# Sheet_1_2025-11-09.net
KiCad netlist of a schematic drawn in Altium Designer
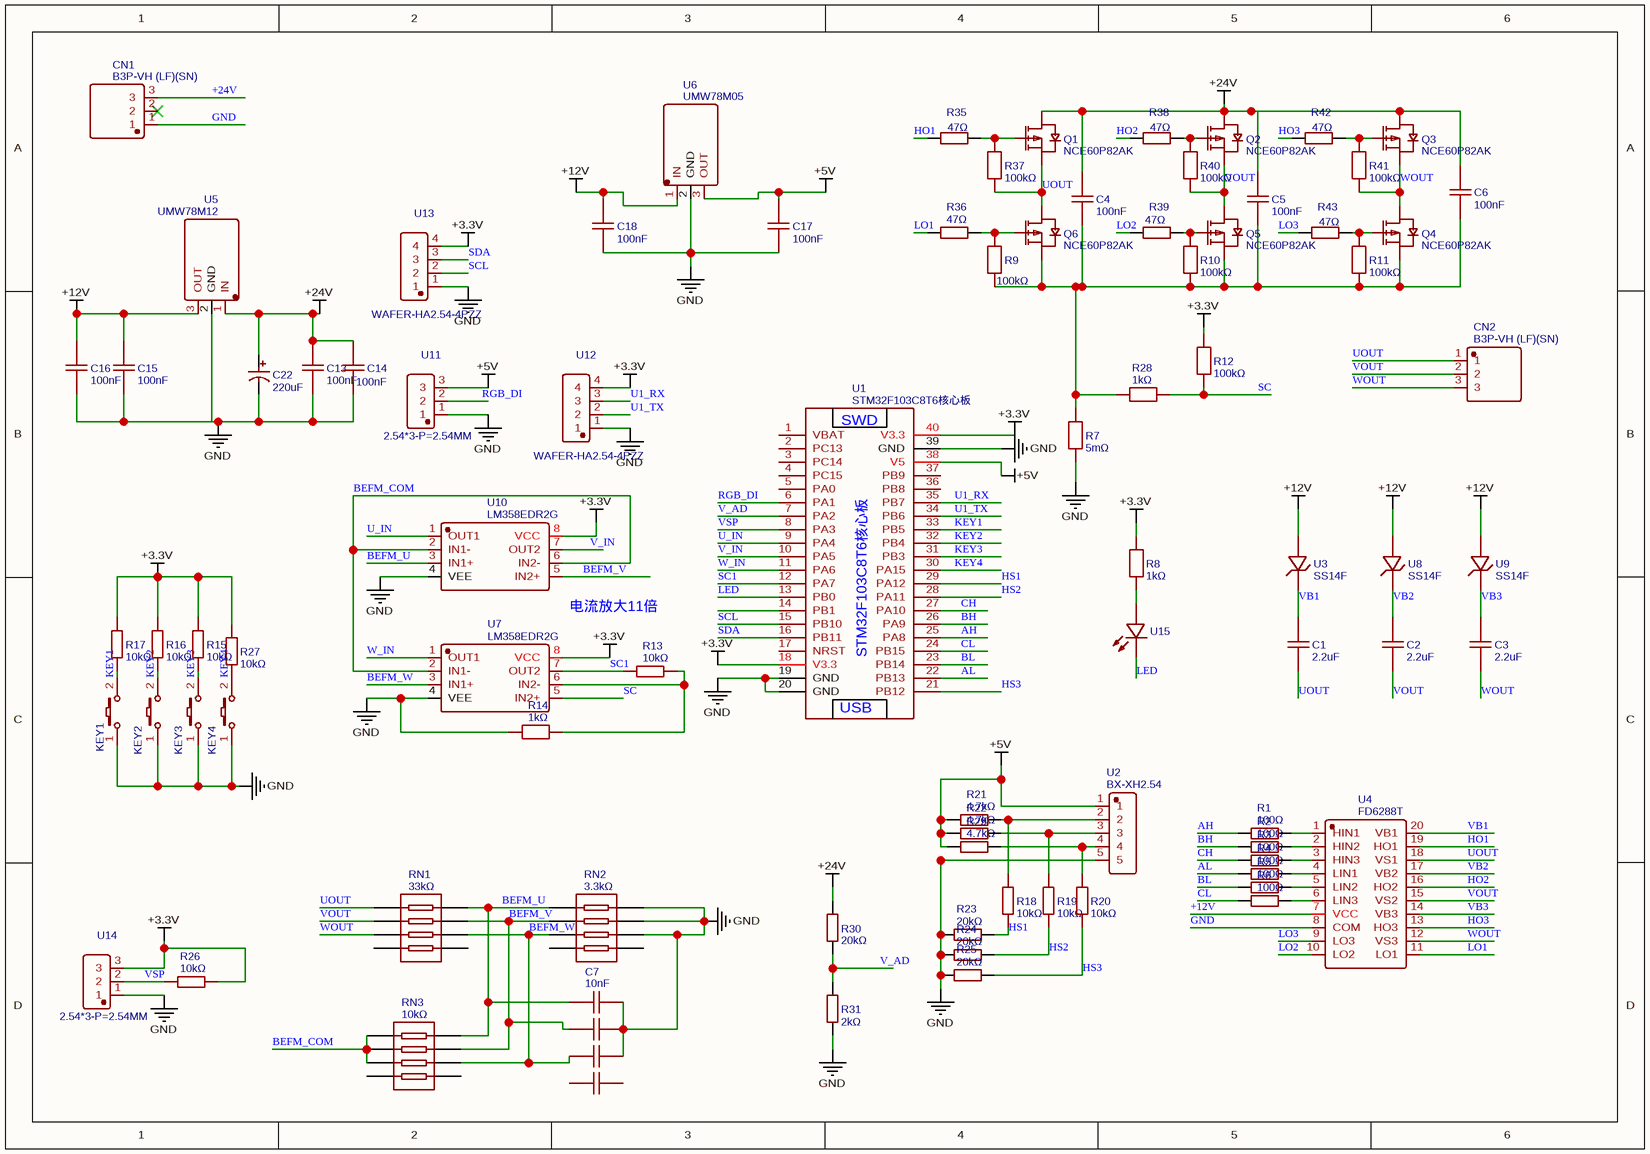
[diagram p0: Sheet_1_2025-11-09.schdoc]

(export (version "E")
  (design (tool "Eeschema 10.0.6"))
  (components
    (comp (ref "C1")
      (value "2.2uF")
      (fields
        (field (name "MANUFACTURER") "CCTC(三环)")
        (field (name "MANUFACTURER PART") "TCC0805X5R225K250FT")
        (field (name "CONTRIBUTOR") "lcsc")
      )
      (libsource (lib "altium-import") (part "root_1_2.2uF_"))
    )
    (comp (ref "C2")
      (value "2.2uF")
      (fields
        (field (name "MANUFACTURER") "CCTC(三环)")
        (field (name "MANUFACTURER PART") "TCC0805X5R225K250FT")
        (field (name "CONTRIBUTOR") "lcsc")
      )
      (libsource (lib "altium-import") (part "root_1_2.2uF_"))
    )
    (comp (ref "C3")
      (value "2.2uF")
      (fields
        (field (name "MANUFACTURER") "CCTC(三环)")
        (field (name "MANUFACTURER PART") "TCC0805X5R225K250FT")
        (field (name "CONTRIBUTOR") "lcsc")
      )
      (libsource (lib "altium-import") (part "root_1_2.2uF_"))
    )
    (comp (ref "C4")
      (value "100nF")
      (fields
        (field (name "MANUFACTURER PART") "CT41-0603-2F4-50V-0.1uF-M(N)")
        (field (name "CONTRIBUTOR") "LCSC")
      )
      (libsource (lib "altium-import") (part "root_0_100nF_"))
    )
    (comp (ref "C5")
      (value "100nF")
      (fields
        (field (name "MANUFACTURER PART") "CT41-0603-2F4-50V-0.1uF-M(N)")
        (field (name "CONTRIBUTOR") "LCSC")
      )
      (libsource (lib "altium-import") (part "root_0_100nF_"))
    )
    (comp (ref "C6")
      (value "100nF")
      (fields
        (field (name "MANUFACTURER PART") "CT41-0603-2F4-50V-0.1uF-M(N)")
        (field (name "CONTRIBUTOR") "LCSC")
      )
      (libsource (lib "altium-import") (part "root_0_100nF_"))
    )
    (comp (ref "C7")
      (value "10nF")
      (fields
        (field (name "MANUFACTURER") "YAGEO(国巨)")
        (field (name "MANUFACTURER PART") "CA0612KRX7R9BB103")
        (field (name "CONTRIBUTOR") "LCSC")
      )
      (libsource (lib "altium-import") (part "root_1_10nF_"))
    )
    (comp (ref "C13")
      (value "100nF")
      (fields
        (field (name "MANUFACTURER") "XINNA(新纳)")
        (field (name "MANUFACTURER PART") "CT063X7R104KNTD")
        (field (name "CONTRIBUTOR") "lcsc")
      )
      (libsource (lib "altium-import") (part "root_1_100nF_"))
    )
    (comp (ref "C14")
      (value "100nF")
      (fields
        (field (name "MANUFACTURER") "XINNA(新纳)")
        (field (name "MANUFACTURER PART") "CT063X7R104KNTD")
        (field (name "CONTRIBUTOR") "lcsc")
      )
      (libsource (lib "altium-import") (part "root_1_100nF_"))
    )
    (comp (ref "C15")
      (value "100nF")
      (fields
        (field (name "MANUFACTURER") "XINNA(新纳)")
        (field (name "MANUFACTURER PART") "CT063X7R104KNTD")
        (field (name "CONTRIBUTOR") "lcsc")
      )
      (libsource (lib "altium-import") (part "root_1_100nF_"))
    )
    (comp (ref "C16")
      (value "100nF")
      (fields
        (field (name "MANUFACTURER") "XINNA(新纳)")
        (field (name "MANUFACTURER PART") "CT063X7R104KNTD")
        (field (name "CONTRIBUTOR") "lcsc")
      )
      (libsource (lib "altium-import") (part "root_1_100nF_"))
    )
    (comp (ref "C17")
      (value "100nF")
      (fields
        (field (name "MANUFACTURER") "XINNA(新纳)")
        (field (name "MANUFACTURER PART") "CT063X7R104KNTD")
        (field (name "CONTRIBUTOR") "lcsc")
      )
      (libsource (lib "altium-import") (part "root_1_100nF_"))
    )
    (comp (ref "C18")
      (value "100nF")
      (fields
        (field (name "MANUFACTURER") "XINNA(新纳)")
        (field (name "MANUFACTURER PART") "CT063X7R104KNTD")
        (field (name "CONTRIBUTOR") "lcsc")
      )
      (libsource (lib "altium-import") (part "root_1_100nF_"))
    )
    (comp (ref "C22")
      (value "220uF")
      (fields
        (field (name "MANUFACTURER") "rubycon(红宝石)")
        (field (name "MANUFACTURER PART") "100PX220MEFC12.5X20")
      )
      (libsource (lib "altium-import") (part "root_3_220uF_"))
    )
    (comp (ref "CN1")
      (value "B3P-VH (LF)(SN)")
      (fields
        (field (name "MANUFACTURER") "JST")
        (field (name "MANUFACTURER PART") "B3P-VH(LF)(SN)")
        (field (name "CONTRIBUTOR") "LCSC")
      )
      (libsource (lib "altium-import") (part "root_2_B3P-VH (LF)(SN)_"))
    )
    (comp (ref "CN2")
      (value "B3P-VH (LF)(SN)")
      (fields
        (field (name "MANUFACTURER") "JST")
        (field (name "MANUFACTURER PART") "B3P-VH(LF)(SN)")
        (field (name "CONTRIBUTOR") "LCSC")
      )
      (libsource (lib "altium-import") (part "root_0_B3P-VH (LF)(SN)_"))
    )
    (comp (ref "KEY1")
      (value "K2-3.6×6.1_SMD")
      (fields (field (name "MANUFACTURER PART") "K2-1107ST-A4SW-06") (field (name "CONTRIBUTOR") "LCEDA_Lib"))
      (libsource (lib "altium-import") (part "root_1_K2-3.6×6.1_SMD_"))
    )
    (comp (ref "KEY2")
      (value "K2-3.6×6.1_SMD")
      (fields (field (name "MANUFACTURER PART") "K2-1107ST-A4SW-06") (field (name "CONTRIBUTOR") "LCEDA_Lib"))
      (libsource (lib "altium-import") (part "root_1_K2-3.6×6.1_SMD_"))
    )
    (comp (ref "KEY3")
      (value "K2-3.6×6.1_SMD")
      (fields (field (name "MANUFACTURER PART") "K2-1107ST-A4SW-06") (field (name "CONTRIBUTOR") "LCEDA_Lib"))
      (libsource (lib "altium-import") (part "root_1_K2-3.6×6.1_SMD_"))
    )
    (comp (ref "KEY4")
      (value "K2-3.6×6.1_SMD")
      (fields (field (name "MANUFACTURER PART") "K2-1107ST-A4SW-06") (field (name "CONTRIBUTOR") "LCEDA_Lib"))
      (libsource (lib "altium-import") (part "root_1_K2-3.6×6.1_SMD_"))
    )
    (comp (ref "Q1")
      (value "NCE60P82AK")
      (fields (field (name "MANUFACTURER") "NCE(无锡新洁能)") (field (name "CONTRIBUTOR") "lcsc"))
      (libsource (lib "altium-import") (part "root_0_NCE60P82AK_"))
    )
    (comp (ref "Q2")
      (value "NCE60P82AK")
      (fields (field (name "MANUFACTURER") "NCE(无锡新洁能)") (field (name "CONTRIBUTOR") "lcsc"))
      (libsource (lib "altium-import") (part "root_0_NCE60P82AK_"))
    )
    (comp (ref "Q3")
      (value "NCE60P82AK")
      (fields (field (name "MANUFACTURER") "NCE(无锡新洁能)") (field (name "CONTRIBUTOR") "lcsc"))
      (libsource (lib "altium-import") (part "root_0_NCE60P82AK_"))
    )
    (comp (ref "Q4")
      (value "NCE60P82AK")
      (fields (field (name "MANUFACTURER") "NCE(无锡新洁能)") (field (name "CONTRIBUTOR") "lcsc"))
      (libsource (lib "altium-import") (part "root_0_NCE60P82AK_"))
    )
    (comp (ref "Q5")
      (value "NCE60P82AK")
      (fields (field (name "MANUFACTURER") "NCE(无锡新洁能)") (field (name "CONTRIBUTOR") "lcsc"))
      (libsource (lib "altium-import") (part "root_0_NCE60P82AK_"))
    )
    (comp (ref "Q6")
      (value "NCE60P82AK")
      (fields (field (name "MANUFACTURER") "NCE(无锡新洁能)") (field (name "CONTRIBUTOR") "lcsc"))
      (libsource (lib "altium-import") (part "root_0_NCE60P82AK_"))
    )
    (comp (ref "R1")
      (value "100Ω")
      (fields
        (field (name "MANUFACTURER") "UNI-ROYAL(厚声)")
        (field (name "MANUFACTURER PART") "0603WAF1000T5E")
      )
      (libsource (lib "altium-import") (part "root_0_100Ω_"))
    )
    (comp (ref "R2")
      (value "100Ω")
      (fields
        (field (name "MANUFACTURER") "UNI-ROYAL(厚声)")
        (field (name "MANUFACTURER PART") "0603WAF1000T5E")
      )
      (libsource (lib "altium-import") (part "root_0_100Ω_"))
    )
    (comp (ref "R3")
      (value "100Ω")
      (fields
        (field (name "MANUFACTURER") "UNI-ROYAL(厚声)")
        (field (name "MANUFACTURER PART") "0603WAF1000T5E")
      )
      (libsource (lib "altium-import") (part "root_0_100Ω_"))
    )
    (comp (ref "R4")
      (value "100Ω")
      (fields
        (field (name "MANUFACTURER") "UNI-ROYAL(厚声)")
        (field (name "MANUFACTURER PART") "0603WAF1000T5E")
      )
      (libsource (lib "altium-import") (part "root_0_100Ω_"))
    )
    (comp (ref "R5")
      (value "100Ω")
      (fields
        (field (name "MANUFACTURER") "UNI-ROYAL(厚声)")
        (field (name "MANUFACTURER PART") "0603WAF1000T5E")
      )
      (libsource (lib "altium-import") (part "root_0_100Ω_"))
    )
    (comp (ref "R6")
      (value "100Ω")
      (fields
        (field (name "MANUFACTURER") "UNI-ROYAL(厚声)")
        (field (name "MANUFACTURER PART") "0603WAF1000T5E")
      )
      (libsource (lib "altium-import") (part "root_0_100Ω_"))
    )
    (comp (ref "R7")
      (value "5mΩ")
      (fields
        (field (name "MANUFACTURER") "Milliohm(毫欧)")
        (field (name "MANUFACTURER PART") "HoLR2512-1.5W-100mR-1%-15ppm")
        (field (name "CONTRIBUTOR") "LCSC")
      )
      (libsource (lib "altium-import") (part "root_1_5mΩ_"))
    )
    (comp (ref "R8")
      (value "1kΩ")
      (fields
        (field (name "MANUFACTURER") "TE Connectivity(泰科电子)")
        (field (name "MANUFACTURER PART") "CPF0603B10KE1")
        (field (name "CONTRIBUTOR") "lcsc")
      )
      (libsource (lib "altium-import") (part "root_1_1kΩ_"))
    )
    (comp (ref "R9")
      (value "100kΩ")
      (fields
        (field (name "MANUFACTURER") "Milliohm(毫欧)")
        (field (name "MANUFACTURER PART") "HoAR0603-1/10W-100KR-1%-TCR25")
        (field (name "CONTRIBUTOR") "lcsc")
      )
      (libsource (lib "altium-import") (part "root_1_100kΩ_"))
    )
    (comp (ref "R10")
      (value "100kΩ")
      (fields
        (field (name "MANUFACTURER") "Milliohm(毫欧)")
        (field (name "MANUFACTURER PART") "HoAR0603-1/10W-100KR-1%-TCR25")
        (field (name "CONTRIBUTOR") "lcsc")
      )
      (libsource (lib "altium-import") (part "root_1_100kΩ_"))
    )
    (comp (ref "R11")
      (value "100kΩ")
      (fields
        (field (name "MANUFACTURER") "Milliohm(毫欧)")
        (field (name "MANUFACTURER PART") "HoAR0603-1/10W-100KR-1%-TCR25")
        (field (name "CONTRIBUTOR") "lcsc")
      )
      (libsource (lib "altium-import") (part "root_1_100kΩ_"))
    )
    (comp (ref "R12")
      (value "100kΩ")
      (fields
        (field (name "MANUFACTURER") "TE Connectivity(泰科电子)")
        (field (name "MANUFACTURER PART") "CPF0603B10KE1")
        (field (name "CONTRIBUTOR") "lcsc")
      )
      (libsource (lib "altium-import") (part "root_1_100kΩ_"))
    )
    (comp (ref "R13")
      (value "10kΩ")
      (fields
        (field (name "MANUFACTURER") "Tyohm(幸亚电阻)")
        (field (name "MANUFACTURER PART") "RMC060310KFN")
        (field (name "CONTRIBUTOR") "LCSC")
      )
      (libsource (lib "altium-import") (part "root_0_10kΩ_"))
    )
    (comp (ref "R14")
      (value "1kΩ")
      (fields
        (field (name "MANUFACTURER") "VO(翔胜)")
        (field (name "MANUFACTURER PART") "FCR0603F1K")
        (field (name "CONTRIBUTOR") "lcsc")
      )
      (libsource (lib "altium-import") (part "root_0_1kΩ_"))
    )
    (comp (ref "R15")
      (value "10kΩ")
      (fields
        (field (name "MANUFACTURER") "Tyohm(幸亚电阻)")
        (field (name "MANUFACTURER PART") "RMC060310KFN")
        (field (name "CONTRIBUTOR") "LCSC")
      )
      (libsource (lib "altium-import") (part "root_1_10kΩ_"))
    )
    (comp (ref "R16")
      (value "10kΩ")
      (fields
        (field (name "MANUFACTURER") "Tyohm(幸亚电阻)")
        (field (name "MANUFACTURER PART") "RMC060310KFN")
        (field (name "CONTRIBUTOR") "LCSC")
      )
      (libsource (lib "altium-import") (part "root_1_10kΩ_"))
    )
    (comp (ref "R17")
      (value "10kΩ")
      (fields
        (field (name "MANUFACTURER") "Tyohm(幸亚电阻)")
        (field (name "MANUFACTURER PART") "RMC060310KFN")
        (field (name "CONTRIBUTOR") "LCSC")
      )
      (libsource (lib "altium-import") (part "root_1_10kΩ_"))
    )
    (comp (ref "R18")
      (value "10kΩ")
      (fields
        (field (name "MANUFACTURER") "Tyohm(幸亚电阻)")
        (field (name "MANUFACTURER PART") "RMC060310KFN")
        (field (name "CONTRIBUTOR") "LCSC")
      )
      (libsource (lib "altium-import") (part "root_1_10kΩ_"))
    )
    (comp (ref "R19")
      (value "10kΩ")
      (fields
        (field (name "MANUFACTURER") "Tyohm(幸亚电阻)")
        (field (name "MANUFACTURER PART") "RMC060310KFN")
        (field (name "CONTRIBUTOR") "LCSC")
      )
      (libsource (lib "altium-import") (part "root_1_10kΩ_"))
    )
    (comp (ref "R20")
      (value "10kΩ")
      (fields
        (field (name "MANUFACTURER") "Tyohm(幸亚电阻)")
        (field (name "MANUFACTURER PART") "RMC060310KFN")
        (field (name "CONTRIBUTOR") "LCSC")
      )
      (libsource (lib "altium-import") (part "root_1_10kΩ_"))
    )
    (comp (ref "R21")
      (value "4.7kΩ")
      (fields
        (field (name "MANUFACTURER") "UNI-ROYAL(厚声)")
        (field (name "MANUFACTURER PART") "0603WAF4701T5E")
      )
      (libsource (lib "altium-import") (part "root_2_4.7kΩ_"))
    )
    (comp (ref "R22")
      (value "4.7kΩ")
      (fields
        (field (name "MANUFACTURER") "UNI-ROYAL(厚声)")
        (field (name "MANUFACTURER PART") "0603WAF4701T5E")
      )
      (libsource (lib "altium-import") (part "root_2_4.7kΩ_"))
    )
    (comp (ref "R23")
      (value "20kΩ")
      (fields
        (field (name "MANUFACTURER") "UNI-ROYAL(厚声)")
        (field (name "MANUFACTURER PART") "0603WAF2002T5E")
      )
      (libsource (lib "altium-import") (part "root_2_20kΩ_"))
    )
    (comp (ref "R24")
      (value "20kΩ")
      (fields
        (field (name "MANUFACTURER") "UNI-ROYAL(厚声)")
        (field (name "MANUFACTURER PART") "0603WAF2002T5E")
      )
      (libsource (lib "altium-import") (part "root_2_20kΩ_"))
    )
    (comp (ref "R25")
      (value "20kΩ")
      (fields
        (field (name "MANUFACTURER") "UNI-ROYAL(厚声)")
        (field (name "MANUFACTURER PART") "0603WAF2002T5E")
      )
      (libsource (lib "altium-import") (part "root_2_20kΩ_"))
    )
    (comp (ref "R26")
      (value "10kΩ")
      (fields
        (field (name "MANUFACTURER") "Tyohm(幸亚电阻)")
        (field (name "MANUFACTURER PART") "RMC060310KFN")
        (field (name "CONTRIBUTOR") "LCSC")
      )
      (libsource (lib "altium-import") (part "root_2_10kΩ_"))
    )
    (comp (ref "R27")
      (value "10kΩ")
      (fields
        (field (name "MANUFACTURER") "Tyohm(幸亚电阻)")
        (field (name "MANUFACTURER PART") "RMC060310KFN")
        (field (name "CONTRIBUTOR") "LCSC")
      )
      (libsource (lib "altium-import") (part "root_1_10kΩ_"))
    )
    (comp (ref "R28")
      (value "1kΩ")
      (fields
        (field (name "MANUFACTURER") "TE Connectivity(泰科电子)")
        (field (name "MANUFACTURER PART") "CPF0603B10KE1")
        (field (name "CONTRIBUTOR") "lcsc")
      )
      (libsource (lib "altium-import") (part "root_0_1kΩ_"))
    )
    (comp (ref "R29")
      (value "4.7kΩ")
      (fields
        (field (name "MANUFACTURER") "UNI-ROYAL(厚声)")
        (field (name "MANUFACTURER PART") "0603WAF4701T5E")
      )
      (libsource (lib "altium-import") (part "root_2_4.7kΩ_"))
    )
    (comp (ref "R30")
      (value "20kΩ")
      (fields
        (field (name "MANUFACTURER") "UNI-ROYAL(厚声)")
        (field (name "MANUFACTURER PART") "0603WAF2002T5E")
      )
      (libsource (lib "altium-import") (part "root_1_20kΩ_"))
    )
    (comp (ref "R31")
      (value "2kΩ")
      (fields
        (field (name "MANUFACTURER") "UNI-ROYAL(厚声)")
        (field (name "MANUFACTURER PART") "0603WAF2001T5E")
      )
      (libsource (lib "altium-import") (part "root_1_2kΩ_"))
    )
    (comp (ref "R35")
      (value "47Ω")
      (fields
        (field (name "MANUFACTURER") "UNI-ROYAL(厚声)")
        (field (name "MANUFACTURER PART") "0603WAF470JT5E")
      )
      (libsource (lib "altium-import") (part "root_0_47Ω_"))
    )
    (comp (ref "R36")
      (value "47Ω")
      (fields
        (field (name "MANUFACTURER") "UNI-ROYAL(厚声)")
        (field (name "MANUFACTURER PART") "0603WAF470JT5E")
      )
      (libsource (lib "altium-import") (part "root_0_47Ω_"))
    )
    (comp (ref "R37")
      (value "100kΩ")
      (fields
        (field (name "MANUFACTURER") "Milliohm(毫欧)")
        (field (name "MANUFACTURER PART") "HoAR0603-1/10W-100KR-1%-TCR25")
        (field (name "CONTRIBUTOR") "lcsc")
      )
      (libsource (lib "altium-import") (part "root_1_100kΩ_"))
    )
    (comp (ref "R38")
      (value "47Ω")
      (fields
        (field (name "MANUFACTURER") "UNI-ROYAL(厚声)")
        (field (name "MANUFACTURER PART") "0603WAF470JT5E")
      )
      (libsource (lib "altium-import") (part "root_0_47Ω_"))
    )
    (comp (ref "R39")
      (value "47Ω")
      (fields
        (field (name "MANUFACTURER") "UNI-ROYAL(厚声)")
        (field (name "MANUFACTURER PART") "0603WAF470JT5E")
      )
      (libsource (lib "altium-import") (part "root_0_47Ω_"))
    )
    (comp (ref "R40")
      (value "100kΩ")
      (fields
        (field (name "MANUFACTURER") "Milliohm(毫欧)")
        (field (name "MANUFACTURER PART") "HoAR0603-1/10W-100KR-1%-TCR25")
        (field (name "CONTRIBUTOR") "lcsc")
      )
      (libsource (lib "altium-import") (part "root_1_100kΩ_"))
    )
    (comp (ref "R41")
      (value "100kΩ")
      (fields
        (field (name "MANUFACTURER") "Milliohm(毫欧)")
        (field (name "MANUFACTURER PART") "HoAR0603-1/10W-100KR-1%-TCR25")
        (field (name "CONTRIBUTOR") "lcsc")
      )
      (libsource (lib "altium-import") (part "root_1_100kΩ_"))
    )
    (comp (ref "R42")
      (value "47Ω")
      (fields
        (field (name "MANUFACTURER") "UNI-ROYAL(厚声)")
        (field (name "MANUFACTURER PART") "0603WAF470JT5E")
      )
      (libsource (lib "altium-import") (part "root_0_47Ω_"))
    )
    (comp (ref "R43")
      (value "47Ω")
      (fields
        (field (name "MANUFACTURER") "UNI-ROYAL(厚声)")
        (field (name "MANUFACTURER PART") "0603WAF470JT5E")
      )
      (libsource (lib "altium-import") (part "root_0_47Ω_"))
    )
    (comp (ref "RN1")
      (value "33kΩ")
      (fields
        (field (name "MANUFACTURER") "UNI-ROYAL(厚声)")
        (field (name "MANUFACTURER PART") "4D03WGJ0333T5E")
      )
      (libsource (lib "altium-import") (part "root_0_33kΩ_"))
    )
    (comp (ref "RN2")
      (value "3.3kΩ")
      (fields
        (field (name "MANUFACTURER") "UNI-ROYAL(厚声)")
        (field (name "MANUFACTURER PART") "4D03WGJ0333T5E")
      )
      (libsource (lib "altium-import") (part "root_0_3.3kΩ_"))
    )
    (comp (ref "RN3")
      (value "10kΩ")
      (fields
        (field (name "MANUFACTURER") "FH(风华)")
        (field (name "MANUFACTURER PART") "RC-ML08W103JT")
        (field (name "CONTRIBUTOR") "LCSC")
      )
      (libsource (lib "") (part "root_1_10kΩ__1"))
    )
    (comp (ref "U1")
      (value "STM32F103C8T6核心板")
      (fields
        (field (name "MANUFACTURER") "无")
        (field (name "MANUFACTURER PART") "STM32F103C8T6最小系统模块")
        (field (name "SUBPART_NO") "1")
        (field (name "CONTRIBUTOR") "Kolin")
      )
      (libsource (lib "altium-import") (part "root_0_STM32F103C8T6核心板_"))
    )
    (comp (ref "U2")
      (value "BX-XH2.54")
      (fields
        (field (name "MANUFACTURER") "Bossie(博锡)")
        (field (name "MANUFACTURER PART") "BX-XH2.54-5PZZ")
        (field (name "CONTRIBUTOR") "lcsc")
      )
      (libsource (lib "altium-import") (part "root_0_BX-XH2.54_"))
    )
    (comp (ref "U3")
      (value "SS14F")
      (fields (field (name "MANUFACTURER") "GOODWORK(固得沃克)") (field (name "CONTRIBUTOR") "lcsc"))
      (libsource (lib "altium-import") (part "root_1_SS14F_"))
    )
    (comp (ref "U4")
      (value "FD6288T")
      (fields (field (name "MANUFACTURER") "JSMSEMI(杰盛微)") (field (name "CONTRIBUTOR") "lcsc"))
      (libsource (lib "altium-import") (part "root_0_FD6288T_"))
    )
    (comp (ref "U5")
      (value "UMW78M12")
      (fields
        (field (name "MANUFACTURER") "UMW(友台半导体)")
        (field (name "MANUFACTURER PART") "78M12")
        (field (name "CONTRIBUTOR") "LCSC")
      )
      (libsource (lib "altium-import") (part "root_1_UMW78M12_"))
    )
    (comp (ref "U6")
      (value "UMW78M05")
      (fields
        (field (name "MANUFACTURER") "UMW(友台半导体)")
        (field (name "MANUFACTURER PART") "78M05")
        (field (name "CONTRIBUTOR") "LCSC")
      )
      (libsource (lib "altium-import") (part "root_1_UMW78M05_"))
    )
    (comp (ref "U7")
      (value "LM358EDR2G")
      (fields (field (name "MANUFACTURER") "onsemi(安森美)") (field (name "CONTRIBUTOR") "LCSC"))
      (libsource (lib "altium-import") (part "root_0_LM358EDR2G_"))
    )
    (comp (ref "U8")
      (value "SS14F")
      (fields (field (name "MANUFACTURER") "GOODWORK(固得沃克)") (field (name "CONTRIBUTOR") "lcsc"))
      (libsource (lib "altium-import") (part "root_1_SS14F_"))
    )
    (comp (ref "U9")
      (value "SS14F")
      (fields (field (name "MANUFACTURER") "GOODWORK(固得沃克)") (field (name "CONTRIBUTOR") "lcsc"))
      (libsource (lib "altium-import") (part "root_1_SS14F_"))
    )
    (comp (ref "U10")
      (value "LM358EDR2G")
      (fields (field (name "MANUFACTURER") "onsemi(安森美)") (field (name "CONTRIBUTOR") "LCSC"))
      (libsource (lib "altium-import") (part "root_0_LM358EDR2G_"))
    )
    (comp (ref "U11")
      (value "2.54*3-P=2.54MM")
      (fields (field (name "MANUFACTURER PART") "2.54*3-P=2.54mm") (field (name "CONTRIBUTOR") "LCSC"))
      (libsource (lib "altium-import") (part "root_2_2.54*3-P=2.54MM_"))
    )
    (comp (ref "U12")
      (value "WAFER-HA2.54-4PZZ")
      (fields (field (name "MANUFACTURER") "XUNPU(讯普)") (field (name "CONTRIBUTOR") "lcsc"))
      (libsource (lib "altium-import") (part "root_2_WAFER-HA2.54-4PZZ_"))
    )
    (comp (ref "U13")
      (value "WAFER-HA2.54-4PZZ")
      (fields (field (name "MANUFACTURER") "XUNPU(讯普)") (field (name "CONTRIBUTOR") "lcsc"))
      (libsource (lib "altium-import") (part "root_2_WAFER-HA2.54-4PZZ_"))
    )
    (comp (ref "U14")
      (value "2.54*3-P=2.54MM")
      (fields (field (name "MANUFACTURER PART") "2.54*3-P=2.54mm") (field (name "CONTRIBUTOR") "LCSC"))
      (libsource (lib "altium-import") (part "root_2_2.54*3-P=2.54MM_"))
    )
    (comp (ref "U15")
      (value "KO-0805_C9900066565")
      (fields (field (name "MANUFACTURER PART") "KO-0805") (field (name "CONTRIBUTOR") "lcsc"))
      (libsource (lib "altium-import") (part "root_1_KO-0805_C9900066565_"))
    )
  )
  (nets
    (net (code "1") (name "+3.3V") (class "Default")
      (node (ref "R12") (pin "2") (pinfunction "2_2") (pintype "passive"))
      (node (ref "R15") (pin "2") (pinfunction "2_2") (pintype "passive"))
      (node (ref "R16") (pin "2") (pinfunction "2_2") (pintype "passive"))
      (node (ref "R17") (pin "2") (pinfunction "2_2") (pintype "passive"))
      (node (ref "R26") (pin "1") (pinfunction "1_1") (pintype "passive"))
      (node (ref "R27") (pin "2") (pinfunction "2_2") (pintype "passive"))
      (node (ref "R8") (pin "2") (pinfunction "2_2") (pintype "passive"))
      (node (ref "U1") (pin "18") (pinfunction "V3.3_18") (pintype "passive"))
      (node (ref "U1") (pin "40") (pinfunction "V3.3_40") (pintype "passive"))
      (node (ref "U10") (pin "8") (pinfunction "VCC_8") (pintype "passive"))
      (node (ref "U12") (pin "4") (pinfunction "4_4") (pintype "passive"))
      (node (ref "U13") (pin "4") (pinfunction "4_4") (pintype "passive"))
      (node (ref "U14") (pin "3") (pinfunction "3_3") (pintype "passive"))
      (node (ref "U7") (pin "8") (pinfunction "VCC_8") (pintype "passive"))
    )
    (net (code "2") (name "+5V") (class "Default")
      (node (ref "C17") (pin "2") (pinfunction "2_2") (pintype "passive"))
      (node (ref "R21") (pin "2") (pinfunction "2_2") (pintype "passive"))
      (node (ref "R22") (pin "2") (pinfunction "2_2") (pintype "passive"))
      (node (ref "R29") (pin "2") (pinfunction "2_2") (pintype "passive"))
      (node (ref "U1") (pin "38") (pinfunction "V5_38") (pintype "passive"))
      (node (ref "U11") (pin "3") (pinfunction "3_3") (pintype "passive"))
      (node (ref "U2") (pin "1") (pinfunction "1_1") (pintype "passive"))
      (node (ref "U6") (pin "3") (pinfunction "OUT_3") (pintype "passive"))
    )
    (net (code "3") (name "+12V") (class "Default")
      (node (ref "C15") (pin "2") (pinfunction "2_2") (pintype "passive"))
      (node (ref "C16") (pin "2") (pinfunction "2_2") (pintype "passive"))
      (node (ref "C18") (pin "2") (pinfunction "2_2") (pintype "passive"))
      (node (ref "U3") (pin "2") (pinfunction "A_2") (pintype "passive"))
      (node (ref "U4") (pin "7") (pinfunction "VCC_7") (pintype "passive"))
      (node (ref "U5") (pin "3") (pinfunction "OUT_3") (pintype "passive"))
      (node (ref "U6") (pin "1") (pinfunction "IN_1") (pintype "passive"))
      (node (ref "U8") (pin "2") (pinfunction "A_2") (pintype "passive"))
      (node (ref "U9") (pin "2") (pinfunction "A_2") (pintype "passive"))
    )
    (net (code "4") (name "+24V") (class "Default")
      (node (ref "C13") (pin "2") (pinfunction "2_2") (pintype "passive"))
      (node (ref "C14") (pin "2") (pinfunction "2_2") (pintype "passive"))
      (node (ref "C22") (pin "1") (pinfunction "1_1") (pintype "passive"))
      (node (ref "C4") (pin "2") (pinfunction "2_2") (pintype "passive"))
      (node (ref "C5") (pin "2") (pinfunction "2_2") (pintype "passive"))
      (node (ref "C6") (pin "2") (pinfunction "2_2") (pintype "passive"))
      (node (ref "CN1") (pin "3") (pinfunction "3_3") (pintype "passive"))
      (node (ref "Q1") (pin "2") (pinfunction "D_2") (pintype "passive"))
      (node (ref "Q2") (pin "2") (pinfunction "D_2") (pintype "passive"))
      (node (ref "Q3") (pin "2") (pinfunction "D_2") (pintype "passive"))
      (node (ref "R30") (pin "2") (pinfunction "2_2") (pintype "passive"))
      (node (ref "U5") (pin "1") (pinfunction "IN_1") (pintype "passive"))
    )
    (net (code "5") (name "/AH") (class "Default")
      (node (ref "R1") (pin "1") (pinfunction "1_1") (pintype "passive"))
      (node (ref "U1") (pin "25") (pinfunction "PA8_25") (pintype "passive"))
    )
    (net (code "6") (name "/AL") (class "Default")
      (node (ref "R4") (pin "1") (pinfunction "1_1") (pintype "passive"))
      (node (ref "U1") (pin "22") (pinfunction "PB13_22") (pintype "passive"))
    )
    (net (code "7") (name "/BEFM_COM") (class "Default")
      (node (ref "RN3") (pin "5") (pinfunction "5_5") (pintype "passive"))
      (node (ref "RN3") (pin "6") (pinfunction "6_6") (pintype "passive"))
      (node (ref "RN3") (pin "7") (pinfunction "7_7") (pintype "passive"))
      (node (ref "U10") (pin "2") (pinfunction "IN1-_2") (pintype "passive"))
      (node (ref "U10") (pin "6") (pinfunction "IN2-_6") (pintype "passive"))
      (node (ref "U7") (pin "2") (pinfunction "IN1-_2") (pintype "passive"))
    )
    (net (code "8") (name "/BEFM_U") (class "Default")
      (node (ref "C7") (pin "5") (pinfunction "5_5") (pintype "passive"))
      (node (ref "RN1") (pin "8") (pinfunction "8_8") (pintype "passive"))
      (node (ref "RN2") (pin "1") (pinfunction "1_1") (pintype "passive"))
      (node (ref "RN3") (pin "4") (pinfunction "4_4") (pintype "passive"))
      (node (ref "U10") (pin "3") (pinfunction "IN1+_3") (pintype "passive"))
    )
    (net (code "9") (name "/BEFM_V") (class "Default")
      (node (ref "C7") (pin "6") (pinfunction "6_6") (pintype "passive"))
      (node (ref "RN1") (pin "7") (pinfunction "7_7") (pintype "passive"))
      (node (ref "RN2") (pin "2") (pinfunction "2_2") (pintype "passive"))
      (node (ref "RN3") (pin "3") (pinfunction "3_3") (pintype "passive"))
      (node (ref "U10") (pin "5") (pinfunction "IN2+_5") (pintype "passive"))
    )
    (net (code "10") (name "/BEFM_W") (class "Default")
      (node (ref "C7") (pin "7") (pinfunction "7_7") (pintype "passive"))
      (node (ref "RN1") (pin "6") (pinfunction "6_6") (pintype "passive"))
      (node (ref "RN2") (pin "3") (pinfunction "3_3") (pintype "passive"))
      (node (ref "RN3") (pin "2") (pinfunction "2_2") (pintype "passive"))
      (node (ref "U7") (pin "3") (pinfunction "IN1+_3") (pintype "passive"))
    )
    (net (code "11") (name "/BH") (class "Default")
      (node (ref "R2") (pin "1") (pinfunction "1_1") (pintype "passive"))
      (node (ref "U1") (pin "26") (pinfunction "PA9_26") (pintype "passive"))
    )
    (net (code "12") (name "/BL") (class "Default")
      (node (ref "R5") (pin "1") (pinfunction "1_1") (pintype "passive"))
      (node (ref "U1") (pin "23") (pinfunction "PB14_23") (pintype "passive"))
    )
    (net (code "13") (name "/CH") (class "Default")
      (node (ref "R3") (pin "1") (pinfunction "1_1") (pintype "passive"))
      (node (ref "U1") (pin "27") (pinfunction "PA10_27") (pintype "passive"))
    )
    (net (code "14") (name "/CL") (class "Default")
      (node (ref "R6") (pin "1") (pinfunction "1_1") (pintype "passive"))
      (node (ref "U1") (pin "24") (pinfunction "PB15_24") (pintype "passive"))
    )
    (net (code "15") (name "/HO1") (class "Default")
      (node (ref "R35") (pin "1") (pinfunction "1_1") (pintype "passive"))
      (node (ref "U4") (pin "19") (pinfunction "HO1_19") (pintype "passive"))
    )
    (net (code "16") (name "/HO2") (class "Default")
      (node (ref "R38") (pin "1") (pinfunction "1_1") (pintype "passive"))
      (node (ref "U4") (pin "16") (pinfunction "HO2_16") (pintype "passive"))
    )
    (net (code "17") (name "/HO3") (class "Default")
      (node (ref "R42") (pin "1") (pinfunction "1_1") (pintype "passive"))
      (node (ref "U4") (pin "13") (pinfunction "HO3_13") (pintype "passive"))
    )
    (net (code "18") (name "/HS1") (class "Default")
      (node (ref "R18") (pin "1") (pinfunction "1_1") (pintype "passive"))
      (node (ref "R23") (pin "1") (pinfunction "1_1") (pintype "passive"))
      (node (ref "U1") (pin "29") (pinfunction "PA12_29") (pintype "passive"))
    )
    (net (code "19") (name "/HS2") (class "Default")
      (node (ref "R19") (pin "1") (pinfunction "1_1") (pintype "passive"))
      (node (ref "R24") (pin "1") (pinfunction "1_1") (pintype "passive"))
      (node (ref "U1") (pin "28") (pinfunction "PA11_28") (pintype "passive"))
    )
    (net (code "20") (name "/HS3") (class "Default")
      (node (ref "R20") (pin "1") (pinfunction "1_1") (pintype "passive"))
      (node (ref "R25") (pin "1") (pinfunction "1_1") (pintype "passive"))
      (node (ref "U1") (pin "21") (pinfunction "PB12_21") (pintype "passive"))
    )
    (net (code "21") (name "/KEY1") (class "Default")
      (node (ref "KEY1") (pin "2") (pinfunction "2_2") (pintype "passive"))
      (node (ref "R17") (pin "1") (pinfunction "1_1") (pintype "passive"))
      (node (ref "U1") (pin "33") (pinfunction "PB5_33") (pintype "passive"))
    )
    (net (code "22") (name "/KEY2") (class "Default")
      (node (ref "KEY2") (pin "2") (pinfunction "2_2") (pintype "passive"))
      (node (ref "R16") (pin "1") (pinfunction "1_1") (pintype "passive"))
      (node (ref "U1") (pin "32") (pinfunction "PB4_32") (pintype "passive"))
    )
    (net (code "23") (name "/KEY3") (class "Default")
      (node (ref "KEY3") (pin "2") (pinfunction "2_2") (pintype "passive"))
      (node (ref "R15") (pin "1") (pinfunction "1_1") (pintype "passive"))
      (node (ref "U1") (pin "31") (pinfunction "PB3_31") (pintype "passive"))
    )
    (net (code "24") (name "/KEY4") (class "Default")
      (node (ref "KEY4") (pin "2") (pinfunction "2_2") (pintype "passive"))
      (node (ref "R27") (pin "1") (pinfunction "1_1") (pintype "passive"))
      (node (ref "U1") (pin "30") (pinfunction "PA15_30") (pintype "passive"))
    )
    (net (code "25") (name "/LED") (class "Default")
      (node (ref "U1") (pin "13") (pinfunction "PB0_13") (pintype "passive"))
      (node (ref "U15") (pin "1") (pinfunction "K_1") (pintype "passive"))
    )
    (net (code "26") (name "/LO1") (class "Default")
      (node (ref "R36") (pin "1") (pinfunction "1_1") (pintype "passive"))
      (node (ref "U4") (pin "11") (pinfunction "LO1_11") (pintype "passive"))
    )
    (net (code "27") (name "/LO2") (class "Default")
      (node (ref "R39") (pin "1") (pinfunction "1_1") (pintype "passive"))
      (node (ref "U4") (pin "10") (pinfunction "LO2_10") (pintype "passive"))
    )
    (net (code "28") (name "/LO3") (class "Default")
      (node (ref "R43") (pin "1") (pinfunction "1_1") (pintype "passive"))
      (node (ref "U4") (pin "9") (pinfunction "LO3_9") (pintype "passive"))
    )
    (net (code "29") (name "/RGB_DI") (class "Default")
      (node (ref "U1") (pin "6") (pinfunction "PA1_6") (pintype "passive"))
      (node (ref "U11") (pin "2") (pinfunction "2_2") (pintype "passive"))
    )
    (net (code "30") (name "/SC") (class "Default")
      (node (ref "R12") (pin "1") (pinfunction "1_1") (pintype "passive"))
      (node (ref "R28") (pin "2") (pinfunction "2_2") (pintype "passive"))
      (node (ref "U7") (pin "5") (pinfunction "IN2+_5") (pintype "passive"))
    )
    (net (code "31") (name "/SC1") (class "Default")
      (node (ref "R13") (pin "1") (pinfunction "1_1") (pintype "passive"))
      (node (ref "U1") (pin "12") (pinfunction "PA7_12") (pintype "passive"))
      (node (ref "U7") (pin "7") (pinfunction "OUT2_7") (pintype "passive"))
    )
    (net (code "32") (name "/SCL") (class "Default")
      (node (ref "U1") (pin "15") (pinfunction "PB10_15") (pintype "passive"))
      (node (ref "U13") (pin "2") (pinfunction "2_2") (pintype "passive"))
    )
    (net (code "33") (name "/SDA") (class "Default")
      (node (ref "U1") (pin "16") (pinfunction "PB11_16") (pintype "passive"))
      (node (ref "U13") (pin "3") (pinfunction "3_3") (pintype "passive"))
    )
    (net (code "34") (name "/U1_RX") (class "Default")
      (node (ref "U1") (pin "35") (pinfunction "PB7_35") (pintype "passive"))
      (node (ref "U12") (pin "3") (pinfunction "3_3") (pintype "passive"))
    )
    (net (code "35") (name "/U1_TX") (class "Default")
      (node (ref "U1") (pin "34") (pinfunction "PB6_34") (pintype "passive"))
      (node (ref "U12") (pin "2") (pinfunction "2_2") (pintype "passive"))
    )
    (net (code "36") (name "/UOUT") (class "Default")
      (node (ref "C1") (pin "1") (pinfunction "1_1") (pintype "passive"))
      (node (ref "CN2") (pin "1") (pinfunction "1_1") (pintype "passive"))
      (node (ref "Q1") (pin "3") (pinfunction "S_3") (pintype "passive"))
      (node (ref "Q6") (pin "2") (pinfunction "D_2") (pintype "passive"))
      (node (ref "R37") (pin "1") (pinfunction "1_1") (pintype "passive"))
      (node (ref "RN1") (pin "1") (pinfunction "1_1") (pintype "passive"))
      (node (ref "U4") (pin "18") (pinfunction "VS1_18") (pintype "passive"))
    )
    (net (code "37") (name "/U_IN") (class "Default")
      (node (ref "U1") (pin "9") (pinfunction "PA4_9") (pintype "passive"))
      (node (ref "U10") (pin "1") (pinfunction "OUT1_1") (pintype "passive"))
    )
    (net (code "38") (name "/VB1") (class "Default")
      (node (ref "C1") (pin "2") (pinfunction "2_2") (pintype "passive"))
      (node (ref "U3") (pin "1") (pinfunction "C_1") (pintype "passive"))
      (node (ref "U4") (pin "20") (pinfunction "VB1_20") (pintype "passive"))
    )
    (net (code "39") (name "/VB2") (class "Default")
      (node (ref "C2") (pin "2") (pinfunction "2_2") (pintype "passive"))
      (node (ref "U4") (pin "17") (pinfunction "VB2_17") (pintype "passive"))
      (node (ref "U8") (pin "1") (pinfunction "C_1") (pintype "passive"))
    )
    (net (code "40") (name "/VB3") (class "Default")
      (node (ref "C3") (pin "2") (pinfunction "2_2") (pintype "passive"))
      (node (ref "U4") (pin "14") (pinfunction "VB3_14") (pintype "passive"))
      (node (ref "U9") (pin "1") (pinfunction "C_1") (pintype "passive"))
    )
    (net (code "41") (name "/VOUT") (class "Default")
      (node (ref "C2") (pin "1") (pinfunction "1_1") (pintype "passive"))
      (node (ref "CN2") (pin "2") (pinfunction "2_2") (pintype "passive"))
      (node (ref "Q2") (pin "3") (pinfunction "S_3") (pintype "passive"))
      (node (ref "Q5") (pin "2") (pinfunction "D_2") (pintype "passive"))
      (node (ref "R40") (pin "1") (pinfunction "1_1") (pintype "passive"))
      (node (ref "RN1") (pin "2") (pinfunction "2_2") (pintype "passive"))
      (node (ref "U4") (pin "15") (pinfunction "VS2_15") (pintype "passive"))
    )
    (net (code "42") (name "/VSP") (class "Default")
      (node (ref "R26") (pin "2") (pinfunction "2_2") (pintype "passive"))
      (node (ref "U1") (pin "8") (pinfunction "PA3_8") (pintype "passive"))
      (node (ref "U14") (pin "2") (pinfunction "2_2") (pintype "passive"))
    )
    (net (code "43") (name "/V_AD") (class "Default")
      (node (ref "R30") (pin "1") (pinfunction "1_1") (pintype "passive"))
      (node (ref "R31") (pin "2") (pinfunction "2_2") (pintype "passive"))
      (node (ref "U1") (pin "7") (pinfunction "PA2_7") (pintype "passive"))
    )
    (net (code "44") (name "/V_IN") (class "Default")
      (node (ref "U1") (pin "10") (pinfunction "PA5_10") (pintype "passive"))
      (node (ref "U10") (pin "7") (pinfunction "OUT2_7") (pintype "passive"))
    )
    (net (code "45") (name "/WOUT") (class "Default")
      (node (ref "C3") (pin "1") (pinfunction "1_1") (pintype "passive"))
      (node (ref "CN2") (pin "3") (pinfunction "3_3") (pintype "passive"))
      (node (ref "Q3") (pin "3") (pinfunction "S_3") (pintype "passive"))
      (node (ref "Q4") (pin "2") (pinfunction "D_2") (pintype "passive"))
      (node (ref "R41") (pin "1") (pinfunction "1_1") (pintype "passive"))
      (node (ref "RN1") (pin "3") (pinfunction "3_3") (pintype "passive"))
      (node (ref "U4") (pin "12") (pinfunction "VS3_12") (pintype "passive"))
    )
    (net (code "46") (name "/W_IN") (class "Default")
      (node (ref "U1") (pin "11") (pinfunction "PA6_11") (pintype "passive"))
      (node (ref "U7") (pin "1") (pinfunction "OUT1_1") (pintype "passive"))
    )
    (net (code "47") (name "GND") (class "Default")
      (node (ref "C13") (pin "1") (pinfunction "1_1") (pintype "passive"))
      (node (ref "C14") (pin "1") (pinfunction "1_1") (pintype "passive"))
      (node (ref "C15") (pin "1") (pinfunction "1_1") (pintype "passive"))
      (node (ref "C16") (pin "1") (pinfunction "1_1") (pintype "passive"))
      (node (ref "C17") (pin "1") (pinfunction "1_1") (pintype "passive"))
      (node (ref "C18") (pin "1") (pinfunction "1_1") (pintype "passive"))
      (node (ref "C22") (pin "2") (pinfunction "2_2") (pintype "passive"))
      (node (ref "C7") (pin "2") (pinfunction "2_2") (pintype "passive"))
      (node (ref "C7") (pin "3") (pinfunction "3_3") (pintype "passive"))
      (node (ref "C7") (pin "4") (pinfunction "4_4") (pintype "passive"))
      (node (ref "CN1") (pin "1") (pinfunction "1_1") (pintype "passive"))
      (node (ref "KEY1") (pin "1") (pinfunction "1_1") (pintype "passive"))
      (node (ref "KEY2") (pin "1") (pinfunction "1_1") (pintype "passive"))
      (node (ref "KEY3") (pin "1") (pinfunction "1_1") (pintype "passive"))
      (node (ref "KEY4") (pin "1") (pinfunction "1_1") (pintype "passive"))
      (node (ref "R14") (pin "1") (pinfunction "1_1") (pintype "passive"))
      (node (ref "R23") (pin "2") (pinfunction "2_2") (pintype "passive"))
      (node (ref "R24") (pin "2") (pinfunction "2_2") (pintype "passive"))
      (node (ref "R25") (pin "2") (pinfunction "2_2") (pintype "passive"))
      (node (ref "R31") (pin "1") (pinfunction "1_1") (pintype "passive"))
      (node (ref "R7") (pin "1") (pinfunction "1_1") (pintype "passive"))
      (node (ref "RN2") (pin "6") (pinfunction "6_6") (pintype "passive"))
      (node (ref "RN2") (pin "7") (pinfunction "7_7") (pintype "passive"))
      (node (ref "RN2") (pin "8") (pinfunction "8_8") (pintype "passive"))
      (node (ref "U1") (pin "19") (pinfunction "GND_19") (pintype "passive"))
      (node (ref "U1") (pin "20") (pinfunction "GND_20") (pintype "passive"))
      (node (ref "U1") (pin "39") (pinfunction "GND_39") (pintype "passive"))
      (node (ref "U10") (pin "4") (pinfunction "VEE_4") (pintype "passive"))
      (node (ref "U11") (pin "1") (pinfunction "1_1") (pintype "passive"))
      (node (ref "U12") (pin "1") (pinfunction "1_1") (pintype "passive"))
      (node (ref "U13") (pin "1") (pinfunction "1_1") (pintype "passive"))
      (node (ref "U14") (pin "1") (pinfunction "1_1") (pintype "passive"))
      (node (ref "U2") (pin "5") (pinfunction "5_5") (pintype "passive"))
      (node (ref "U4") (pin "8") (pinfunction "COM_8") (pintype "passive"))
      (node (ref "U5") (pin "2") (pinfunction "GND_2") (pintype "passive"))
      (node (ref "U6") (pin "2") (pinfunction "GND_2") (pintype "passive"))
      (node (ref "U7") (pin "4") (pinfunction "VEE_4") (pintype "passive"))
    )
    (net (code "48") (name "Net-(Q1-G)") (class "Default")
      (node (ref "Q1") (pin "1") (pinfunction "G_1") (pintype "passive"))
      (node (ref "R35") (pin "2") (pinfunction "2_2") (pintype "passive"))
      (node (ref "R37") (pin "2") (pinfunction "2_2") (pintype "passive"))
    )
    (net (code "49") (name "Net-(Q2-G)") (class "Default")
      (node (ref "Q2") (pin "1") (pinfunction "G_1") (pintype "passive"))
      (node (ref "R38") (pin "2") (pinfunction "2_2") (pintype "passive"))
      (node (ref "R40") (pin "2") (pinfunction "2_2") (pintype "passive"))
    )
    (net (code "50") (name "Net-(Q3-G)") (class "Default")
      (node (ref "Q3") (pin "1") (pinfunction "G_1") (pintype "passive"))
      (node (ref "R41") (pin "2") (pinfunction "2_2") (pintype "passive"))
      (node (ref "R42") (pin "2") (pinfunction "2_2") (pintype "passive"))
    )
    (net (code "51") (name "Net-(Q4-G)") (class "Default")
      (node (ref "Q4") (pin "1") (pinfunction "G_1") (pintype "passive"))
      (node (ref "R11") (pin "2") (pinfunction "2_2") (pintype "passive"))
      (node (ref "R43") (pin "2") (pinfunction "2_2") (pintype "passive"))
    )
    (net (code "52") (name "Net-(Q4-S)") (class "Default")
      (node (ref "C4") (pin "1") (pinfunction "1_1") (pintype "passive"))
      (node (ref "C5") (pin "1") (pinfunction "1_1") (pintype "passive"))
      (node (ref "C6") (pin "1") (pinfunction "1_1") (pintype "passive"))
      (node (ref "Q4") (pin "3") (pinfunction "S_3") (pintype "passive"))
      (node (ref "Q5") (pin "3") (pinfunction "S_3") (pintype "passive"))
      (node (ref "Q6") (pin "3") (pinfunction "S_3") (pintype "passive"))
      (node (ref "R10") (pin "1") (pinfunction "1_1") (pintype "passive"))
      (node (ref "R11") (pin "1") (pinfunction "1_1") (pintype "passive"))
      (node (ref "R28") (pin "1") (pinfunction "1_1") (pintype "passive"))
      (node (ref "R7") (pin "2") (pinfunction "2_2") (pintype "passive"))
      (node (ref "R9") (pin "1") (pinfunction "1_1") (pintype "passive"))
    )
    (net (code "53") (name "Net-(Q5-G)") (class "Default")
      (node (ref "Q5") (pin "1") (pinfunction "G_1") (pintype "passive"))
      (node (ref "R10") (pin "2") (pinfunction "2_2") (pintype "passive"))
      (node (ref "R39") (pin "2") (pinfunction "2_2") (pintype "passive"))
    )
    (net (code "54") (name "Net-(Q6-G)") (class "Default")
      (node (ref "Q6") (pin "1") (pinfunction "G_1") (pintype "passive"))
      (node (ref "R36") (pin "2") (pinfunction "2_2") (pintype "passive"))
      (node (ref "R9") (pin "2") (pinfunction "2_2") (pintype "passive"))
    )
    (net (code "55") (name "Net-(R18-Pad2)") (class "Default")
      (node (ref "R18") (pin "2") (pinfunction "2_2") (pintype "passive"))
      (node (ref "R21") (pin "1") (pinfunction "1_1") (pintype "passive"))
      (node (ref "U2") (pin "2") (pinfunction "2_2") (pintype "passive"))
    )
    (net (code "56") (name "Net-(R19-Pad2)") (class "Default")
      (node (ref "R19") (pin "2") (pinfunction "2_2") (pintype "passive"))
      (node (ref "R22") (pin "1") (pinfunction "1_1") (pintype "passive"))
      (node (ref "U2") (pin "3") (pinfunction "3_3") (pintype "passive"))
    )
    (net (code "57") (name "Net-(R20-Pad2)") (class "Default")
      (node (ref "R20") (pin "2") (pinfunction "2_2") (pintype "passive"))
      (node (ref "R29") (pin "1") (pinfunction "1_1") (pintype "passive"))
      (node (ref "U2") (pin "4") (pinfunction "4_4") (pintype "passive"))
    )
    (net (code "58") (name "Net-(U4-HIN1)") (class "Default")
      (node (ref "R1") (pin "2") (pinfunction "2_2") (pintype "passive"))
      (node (ref "U4") (pin "1") (pinfunction "HIN1_1") (pintype "passive"))
    )
    (net (code "59") (name "Net-(U4-HIN2)") (class "Default")
      (node (ref "R2") (pin "2") (pinfunction "2_2") (pintype "passive"))
      (node (ref "U4") (pin "2") (pinfunction "HIN2_2") (pintype "passive"))
    )
    (net (code "60") (name "Net-(U4-HIN3)") (class "Default")
      (node (ref "R3") (pin "2") (pinfunction "2_2") (pintype "passive"))
      (node (ref "U4") (pin "3") (pinfunction "HIN3_3") (pintype "passive"))
    )
    (net (code "61") (name "Net-(U4-LIN1)") (class "Default")
      (node (ref "R4") (pin "2") (pinfunction "2_2") (pintype "passive"))
      (node (ref "U4") (pin "4") (pinfunction "LIN1_4") (pintype "passive"))
    )
    (net (code "62") (name "Net-(U4-LIN2)") (class "Default")
      (node (ref "R5") (pin "2") (pinfunction "2_2") (pintype "passive"))
      (node (ref "U4") (pin "5") (pinfunction "LIN2_5") (pintype "passive"))
    )
    (net (code "63") (name "Net-(U4-LIN3)") (class "Default")
      (node (ref "R6") (pin "2") (pinfunction "2_2") (pintype "passive"))
      (node (ref "U4") (pin "6") (pinfunction "LIN3_6") (pintype "passive"))
    )
    (net (code "64") (name "Net-(U7-IN2-)") (class "Default")
      (node (ref "R13") (pin "2") (pinfunction "2_2") (pintype "passive"))
      (node (ref "R14") (pin "2") (pinfunction "2_2") (pintype "passive"))
      (node (ref "U7") (pin "6") (pinfunction "IN2-_6") (pintype "passive"))
    )
    (net (code "65") (name "Net-(U15-A)") (class "Default")
      (node (ref "R8") (pin "1") (pinfunction "1_1") (pintype "passive"))
      (node (ref "U15") (pin "2") (pinfunction "A_2") (pintype "passive"))
    )
    (net (code "66") (name "unconnected-(C7-Pad1)") (class "Default")
      (node (ref "C7") (pin "1") (pinfunction "1_1") (pintype "passive"))
    )
    (net (code "67") (name "unconnected-(C7-Pad8)") (class "Default")
      (node (ref "C7") (pin "8") (pinfunction "8_8") (pintype "passive"))
    )
    (net (code "68") (name "unconnected-(CN1-Pad2)") (class "Default")
      (node (ref "CN1") (pin "2") (pinfunction "2_2") (pintype "passive+no_connect"))
    )
    (net (code "69") (name "unconnected-(RN1-Pad4)") (class "Default")
      (node (ref "RN1") (pin "4") (pinfunction "4_4") (pintype "passive"))
    )
    (net (code "70") (name "unconnected-(RN1-Pad5)") (class "Default")
      (node (ref "RN1") (pin "5") (pinfunction "5_5") (pintype "passive"))
    )
    (net (code "71") (name "unconnected-(RN2-Pad4)") (class "Default")
      (node (ref "RN2") (pin "4") (pinfunction "4_4") (pintype "passive"))
    )
    (net (code "72") (name "unconnected-(RN2-Pad5)") (class "Default")
      (node (ref "RN2") (pin "5") (pinfunction "5_5") (pintype "passive"))
    )
    (net (code "73") (name "unconnected-(RN3-Pad1)") (class "Default")
      (node (ref "RN3") (pin "1") (pinfunction "1_1") (pintype "passive"))
    )
    (net (code "74") (name "unconnected-(RN3-Pad8)") (class "Default")
      (node (ref "RN3") (pin "8") (pinfunction "8_8") (pintype "passive"))
    )
    (net (code "75") (name "unconnected-(U1-NRST-Pad17)") (class "Default")
      (node (ref "U1") (pin "17") (pinfunction "NRST_17") (pintype "passive"))
    )
    (net (code "76") (name "unconnected-(U1-PA0-Pad5)") (class "Default")
      (node (ref "U1") (pin "5") (pinfunction "PA0_5") (pintype "passive"))
    )
    (net (code "77") (name "unconnected-(U1-PB1-Pad14)") (class "Default")
      (node (ref "U1") (pin "14") (pinfunction "PB1_14") (pintype "passive"))
    )
    (net (code "78") (name "unconnected-(U1-PB8-Pad36)") (class "Default")
      (node (ref "U1") (pin "36") (pinfunction "PB8_36") (pintype "passive"))
    )
    (net (code "79") (name "unconnected-(U1-PB9-Pad37)") (class "Default")
      (node (ref "U1") (pin "37") (pinfunction "PB9_37") (pintype "passive"))
    )
    (net (code "80") (name "unconnected-(U1-PC13-Pad2)") (class "Default")
      (node (ref "U1") (pin "2") (pinfunction "PC13_2") (pintype "passive"))
    )
    (net (code "81") (name "unconnected-(U1-PC14-Pad3)") (class "Default")
      (node (ref "U1") (pin "3") (pinfunction "PC14_3") (pintype "passive"))
    )
    (net (code "82") (name "unconnected-(U1-PC15-Pad4)") (class "Default")
      (node (ref "U1") (pin "4") (pinfunction "PC15_4") (pintype "passive"))
    )
    (net (code "83") (name "unconnected-(U1-VBAT-Pad1)") (class "Default")
      (node (ref "U1") (pin "1") (pinfunction "VBAT_1") (pintype "passive"))
    )
  )
)
